# unit_schematic_1_1.net
KiCad netlist of a schematic drawn in EAGLE
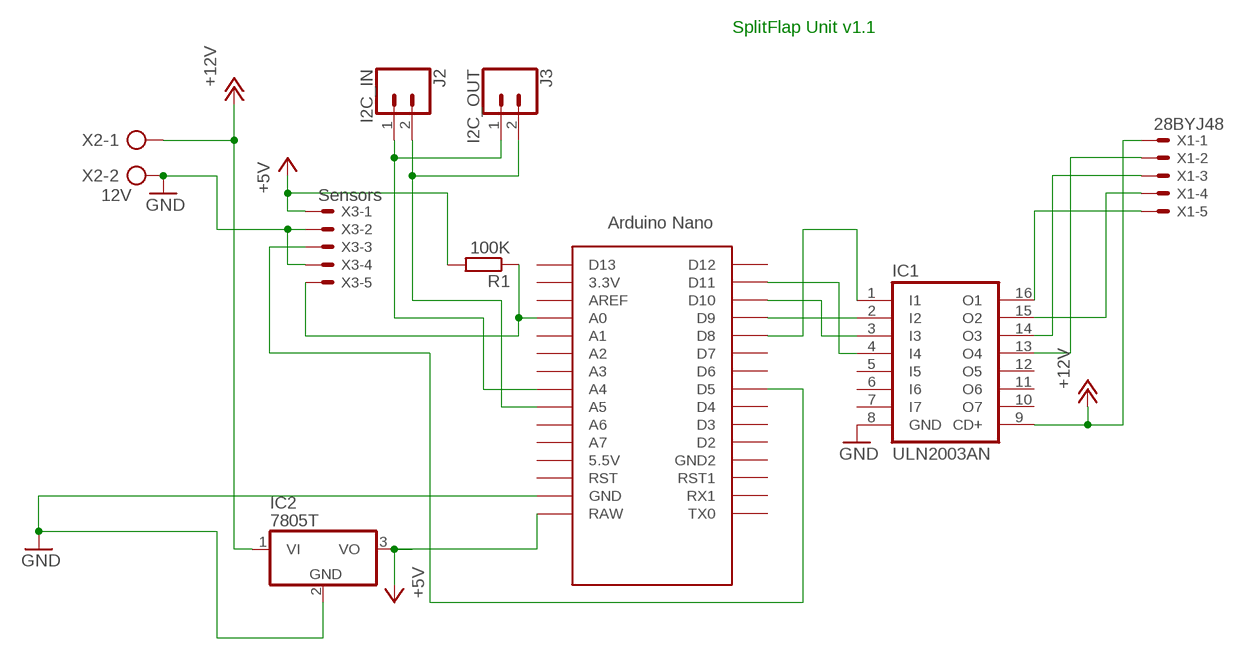
[diagram p0: schematic, sheet 1]

(export (version "E")
  (design (tool "Eeschema 10.0.6"))
  (components
    (comp (ref "IC1")
      (value "ULN2003AN")
      (footprint "eagle-import:DIL16")
      (libsource (lib "eagle-import") (part "ULN2003AN"))
    )
    (comp (ref "IC2")
      (value "7805T")
      (footprint "eagle-import:TO220H")
      (libsource (lib "eagle-import") (part "78T05"))
    )
    (comp (ref "J2")
      (value "I2C_IN")
      (footprint "eagle-import:JST-2-PTH")
      (libsource (lib "eagle-import") (part "CONN_02JST-PTH-2"))
    )
    (comp (ref "J3")
      (value "I2C_OUT")
      (footprint "eagle-import:JST-2-PTH")
      (libsource (lib "eagle-import") (part "CONN_02JST-PTH-2"))
    )
    (comp (ref "R1")
      (value "100K")
      (footprint "eagle-import:0207_10")
      (libsource (lib "eagle-import") (part "R-EU_0207/10"))
    )
    (comp (ref "U$2")
      (value "NANO")
      (footprint "eagle-import:NANO")
      (libsource (lib "eagle-import") (part "NANO"))
    )
    (comp (ref "X1")
      (value "28BYJ48")
      (footprint "eagle-import:JST-XH-05-PACKAGE-ROUND-PAD")
      (libsource (lib "eagle-import") (part "JST-XH-05-PIN-ROUND-PAD"))
    )
    (comp (ref "X2")
      (value "12V")
      (footprint "eagle-import:AK300_2")
      (libsource (lib "eagle-import") (part "AK300/2"))
    )
    (comp (ref "X3")
      (value "Sensors")
      (footprint "eagle-import:JST-XH-05-PACKAGE-ROUND-PAD")
      (libsource (lib "eagle-import") (part "JST-XH-05-PIN-ROUND-PAD"))
    )
  )
  (nets
    (net (code "1") (name "+5V") (class "Default")
      (node (ref "IC2") (pin "3") (pinfunction "VO_3") (pintype "passive"))
      (node (ref "R1") (pin "2") (pinfunction "2_2") (pintype "passive"))
      (node (ref "U$2") (pin "RAW") (pinfunction "RAW_RAW") (pintype "bidirectional"))
      (node (ref "X3") (pin "1") (pinfunction "S_1") (pintype "passive"))
    )
    (net (code "2") (name "+12V") (class "Default")
      (node (ref "IC1") (pin "9") (pinfunction "CD+_9") (pintype "passive"))
      (node (ref "IC2") (pin "1") (pinfunction "VI_1") (pintype "input"))
      (node (ref "X1") (pin "1") (pinfunction "S_1") (pintype "passive"))
      (node (ref "X2") (pin "1") (pinfunction "KL_1") (pintype "passive"))
    )
    (net (code "3") (name "GND") (class "Default")
      (node (ref "IC1") (pin "8") (pinfunction "GND_8") (pintype "power_in"))
      (node (ref "IC2") (pin "2") (pinfunction "GND_2") (pintype "passive"))
      (node (ref "U$2") (pin "GND") (pinfunction "GND_GND") (pintype "bidirectional"))
      (node (ref "X2") (pin "2") (pinfunction "KL_2") (pintype "passive"))
      (node (ref "X3") (pin "2") (pinfunction "S_2") (pintype "passive"))
      (node (ref "X3") (pin "4") (pinfunction "S_4") (pintype "passive"))
    )
    (net (code "4") (name "Net-(IC1-I1)") (class "Default")
      (node (ref "IC1") (pin "1") (pinfunction "I1_1") (pintype "input"))
      (node (ref "U$2") (pin "D8") (pinfunction "D8_D8") (pintype "bidirectional"))
    )
    (net (code "5") (name "Net-(IC1-I2)") (class "Default")
      (node (ref "IC1") (pin "2") (pinfunction "I2_2") (pintype "input"))
      (node (ref "U$2") (pin "D9") (pinfunction "D9_D9") (pintype "bidirectional"))
    )
    (net (code "6") (name "Net-(IC1-I3)") (class "Default")
      (node (ref "IC1") (pin "3") (pinfunction "I3_3") (pintype "input"))
      (node (ref "U$2") (pin "D10") (pinfunction "D10_D10") (pintype "bidirectional"))
    )
    (net (code "7") (name "Net-(IC1-I4)") (class "Default")
      (node (ref "IC1") (pin "4") (pinfunction "I4_4") (pintype "input"))
      (node (ref "U$2") (pin "D11") (pinfunction "D11_D11") (pintype "bidirectional"))
    )
    (net (code "8") (name "Net-(IC1-O1)") (class "Default")
      (node (ref "IC1") (pin "16") (pinfunction "O1_16") (pintype "open_collector"))
      (node (ref "X1") (pin "5") (pinfunction "S_5") (pintype "passive"))
    )
    (net (code "9") (name "Net-(IC1-O2)") (class "Default")
      (node (ref "IC1") (pin "15") (pinfunction "O2_15") (pintype "open_collector"))
      (node (ref "X1") (pin "4") (pinfunction "S_4") (pintype "passive"))
    )
    (net (code "10") (name "Net-(IC1-O3)") (class "Default")
      (node (ref "IC1") (pin "14") (pinfunction "O3_14") (pintype "open_collector"))
      (node (ref "X1") (pin "3") (pinfunction "S_3") (pintype "passive"))
    )
    (net (code "11") (name "Net-(IC1-O4)") (class "Default")
      (node (ref "IC1") (pin "13") (pinfunction "O4_13") (pintype "open_collector"))
      (node (ref "X1") (pin "2") (pinfunction "S_2") (pintype "passive"))
    )
    (net (code "12") (name "Net-(J2-Pad1)") (class "Default")
      (node (ref "J2") (pin "1") (pinfunction "1_1") (pintype "passive"))
      (node (ref "J3") (pin "1") (pinfunction "1_1") (pintype "passive"))
      (node (ref "U$2") (pin "A4") (pinfunction "A4_A4") (pintype "bidirectional"))
    )
    (net (code "13") (name "Net-(J2-Pad2)") (class "Default")
      (node (ref "J2") (pin "2") (pinfunction "2_2") (pintype "passive"))
      (node (ref "J3") (pin "2") (pinfunction "2_2") (pintype "passive"))
      (node (ref "U$2") (pin "A5") (pinfunction "A5_A5") (pintype "bidirectional"))
    )
    (net (code "14") (name "Net-(X3C-S)") (class "Default")
      (node (ref "U$2") (pin "D5") (pinfunction "D5_D5") (pintype "bidirectional"))
      (node (ref "X3") (pin "3") (pinfunction "S_3") (pintype "passive"))
    )
    (net (code "15") (name "Net-(X3E-S)") (class "Default")
      (node (ref "R1") (pin "1") (pinfunction "1_1") (pintype "passive"))
      (node (ref "U$2") (pin "A0") (pinfunction "A0_A0") (pintype "bidirectional"))
      (node (ref "X3") (pin "5") (pinfunction "S_5") (pintype "passive"))
    )
    (net (code "16") (name "unconnected-(IC1-I5-Pad5)") (class "Default")
      (node (ref "IC1") (pin "5") (pinfunction "I5_5") (pintype "input"))
    )
    (net (code "17") (name "unconnected-(IC1-I6-Pad6)") (class "Default")
      (node (ref "IC1") (pin "6") (pinfunction "I6_6") (pintype "input"))
    )
    (net (code "18") (name "unconnected-(IC1-I7-Pad7)") (class "Default")
      (node (ref "IC1") (pin "7") (pinfunction "I7_7") (pintype "input"))
    )
    (net (code "19") (name "unconnected-(IC1-O5-Pad12)") (class "Default")
      (node (ref "IC1") (pin "12") (pinfunction "O5_12") (pintype "open_collector"))
    )
    (net (code "20") (name "unconnected-(IC1-O6-Pad11)") (class "Default")
      (node (ref "IC1") (pin "11") (pinfunction "O6_11") (pintype "open_collector"))
    )
    (net (code "21") (name "unconnected-(IC1-O7-Pad10)") (class "Default")
      (node (ref "IC1") (pin "10") (pinfunction "O7_10") (pintype "open_collector"))
    )
    (net (code "22") (name "unconnected-(U$2-5.5V-Pad5V)") (class "Default")
      (node (ref "U$2") (pin "5V") (pinfunction "5.5V_5V") (pintype "bidirectional"))
    )
    (net (code "23") (name "unconnected-(U$2-GND2-PadGND1)") (class "Default")
      (node (ref "U$2") (pin "GND1") (pinfunction "GND2_GND1") (pintype "bidirectional"))
    )
    (net (code "24") (name "unconnected-(U$2-Pad3.3V)") (class "Default")
      (node (ref "U$2") (pin "3.3V") (pinfunction "3.3V_3.3V") (pintype "bidirectional"))
    )
    (net (code "25") (name "unconnected-(U$2-PadA1)") (class "Default")
      (node (ref "U$2") (pin "A1") (pinfunction "A1_A1") (pintype "bidirectional"))
    )
    (net (code "26") (name "unconnected-(U$2-PadA2)") (class "Default")
      (node (ref "U$2") (pin "A2") (pinfunction "A2_A2") (pintype "bidirectional"))
    )
    (net (code "27") (name "unconnected-(U$2-PadA3)") (class "Default")
      (node (ref "U$2") (pin "A3") (pinfunction "A3_A3") (pintype "bidirectional"))
    )
    (net (code "28") (name "unconnected-(U$2-PadA6)") (class "Default")
      (node (ref "U$2") (pin "A6") (pinfunction "A6_A6") (pintype "bidirectional"))
    )
    (net (code "29") (name "unconnected-(U$2-PadA7)") (class "Default")
      (node (ref "U$2") (pin "A7") (pinfunction "A7_A7") (pintype "bidirectional"))
    )
    (net (code "30") (name "unconnected-(U$2-PadAREF)") (class "Default")
      (node (ref "U$2") (pin "AREF") (pinfunction "AREF_AREF") (pintype "bidirectional"))
    )
    (net (code "31") (name "unconnected-(U$2-PadD2)") (class "Default")
      (node (ref "U$2") (pin "D2") (pinfunction "D2_D2") (pintype "bidirectional"))
    )
    (net (code "32") (name "unconnected-(U$2-PadD3)") (class "Default")
      (node (ref "U$2") (pin "D3") (pinfunction "D3_D3") (pintype "bidirectional"))
    )
    (net (code "33") (name "unconnected-(U$2-PadD4)") (class "Default")
      (node (ref "U$2") (pin "D4") (pinfunction "D4_D4") (pintype "bidirectional"))
    )
    (net (code "34") (name "unconnected-(U$2-PadD6)") (class "Default")
      (node (ref "U$2") (pin "D6") (pinfunction "D6_D6") (pintype "bidirectional"))
    )
    (net (code "35") (name "unconnected-(U$2-PadD7)") (class "Default")
      (node (ref "U$2") (pin "D7") (pinfunction "D7_D7") (pintype "bidirectional"))
    )
    (net (code "36") (name "unconnected-(U$2-PadD12)") (class "Default")
      (node (ref "U$2") (pin "D12") (pinfunction "D12_D12") (pintype "bidirectional"))
    )
    (net (code "37") (name "unconnected-(U$2-PadD13)") (class "Default")
      (node (ref "U$2") (pin "D13") (pinfunction "D13_D13") (pintype "bidirectional"))
    )
    (net (code "38") (name "unconnected-(U$2-PadICSP1)") (class "Default")
      (node (ref "U$2") (pin "ICSP1") (pinfunction "ICSP1_ICSP1") (pintype "bidirectional"))
    )
    (net (code "39") (name "unconnected-(U$2-PadICSP2)") (class "Default")
      (node (ref "U$2") (pin "ICSP2") (pinfunction "ICSP2_ICSP2") (pintype "bidirectional"))
    )
    (net (code "40") (name "unconnected-(U$2-PadICSP3)") (class "Default")
      (node (ref "U$2") (pin "ICSP3") (pinfunction "ICSP3_ICSP3") (pintype "bidirectional"))
    )
    (net (code "41") (name "unconnected-(U$2-PadICSP4)") (class "Default")
      (node (ref "U$2") (pin "ICSP4") (pinfunction "ICSP4_ICSP4") (pintype "bidirectional"))
    )
    (net (code "42") (name "unconnected-(U$2-PadICSP5)") (class "Default")
      (node (ref "U$2") (pin "ICSP5") (pinfunction "ICSP5_ICSP5") (pintype "bidirectional"))
    )
    (net (code "43") (name "unconnected-(U$2-PadICSP6)") (class "Default")
      (node (ref "U$2") (pin "ICSP6") (pinfunction "ICSP6_ICSP6") (pintype "bidirectional"))
    )
    (net (code "44") (name "unconnected-(U$2-PadRST)") (class "Default")
      (node (ref "U$2") (pin "RST") (pinfunction "RST_RST") (pintype "bidirectional"))
    )
    (net (code "45") (name "unconnected-(U$2-PadRST1)") (class "Default")
      (node (ref "U$2") (pin "RST1") (pinfunction "RST1_RST1") (pintype "bidirectional"))
    )
    (net (code "46") (name "unconnected-(U$2-PadRX1)") (class "Default")
      (node (ref "U$2") (pin "RX1") (pinfunction "RX1_RX1") (pintype "bidirectional"))
    )
    (net (code "47") (name "unconnected-(U$2-PadTX0)") (class "Default")
      (node (ref "U$2") (pin "TX0") (pinfunction "TX0_TX0") (pintype "bidirectional"))
    )
  )
)
